# WL-DAC.net
KiCad netlist of a schematic drawn in Altium Designer
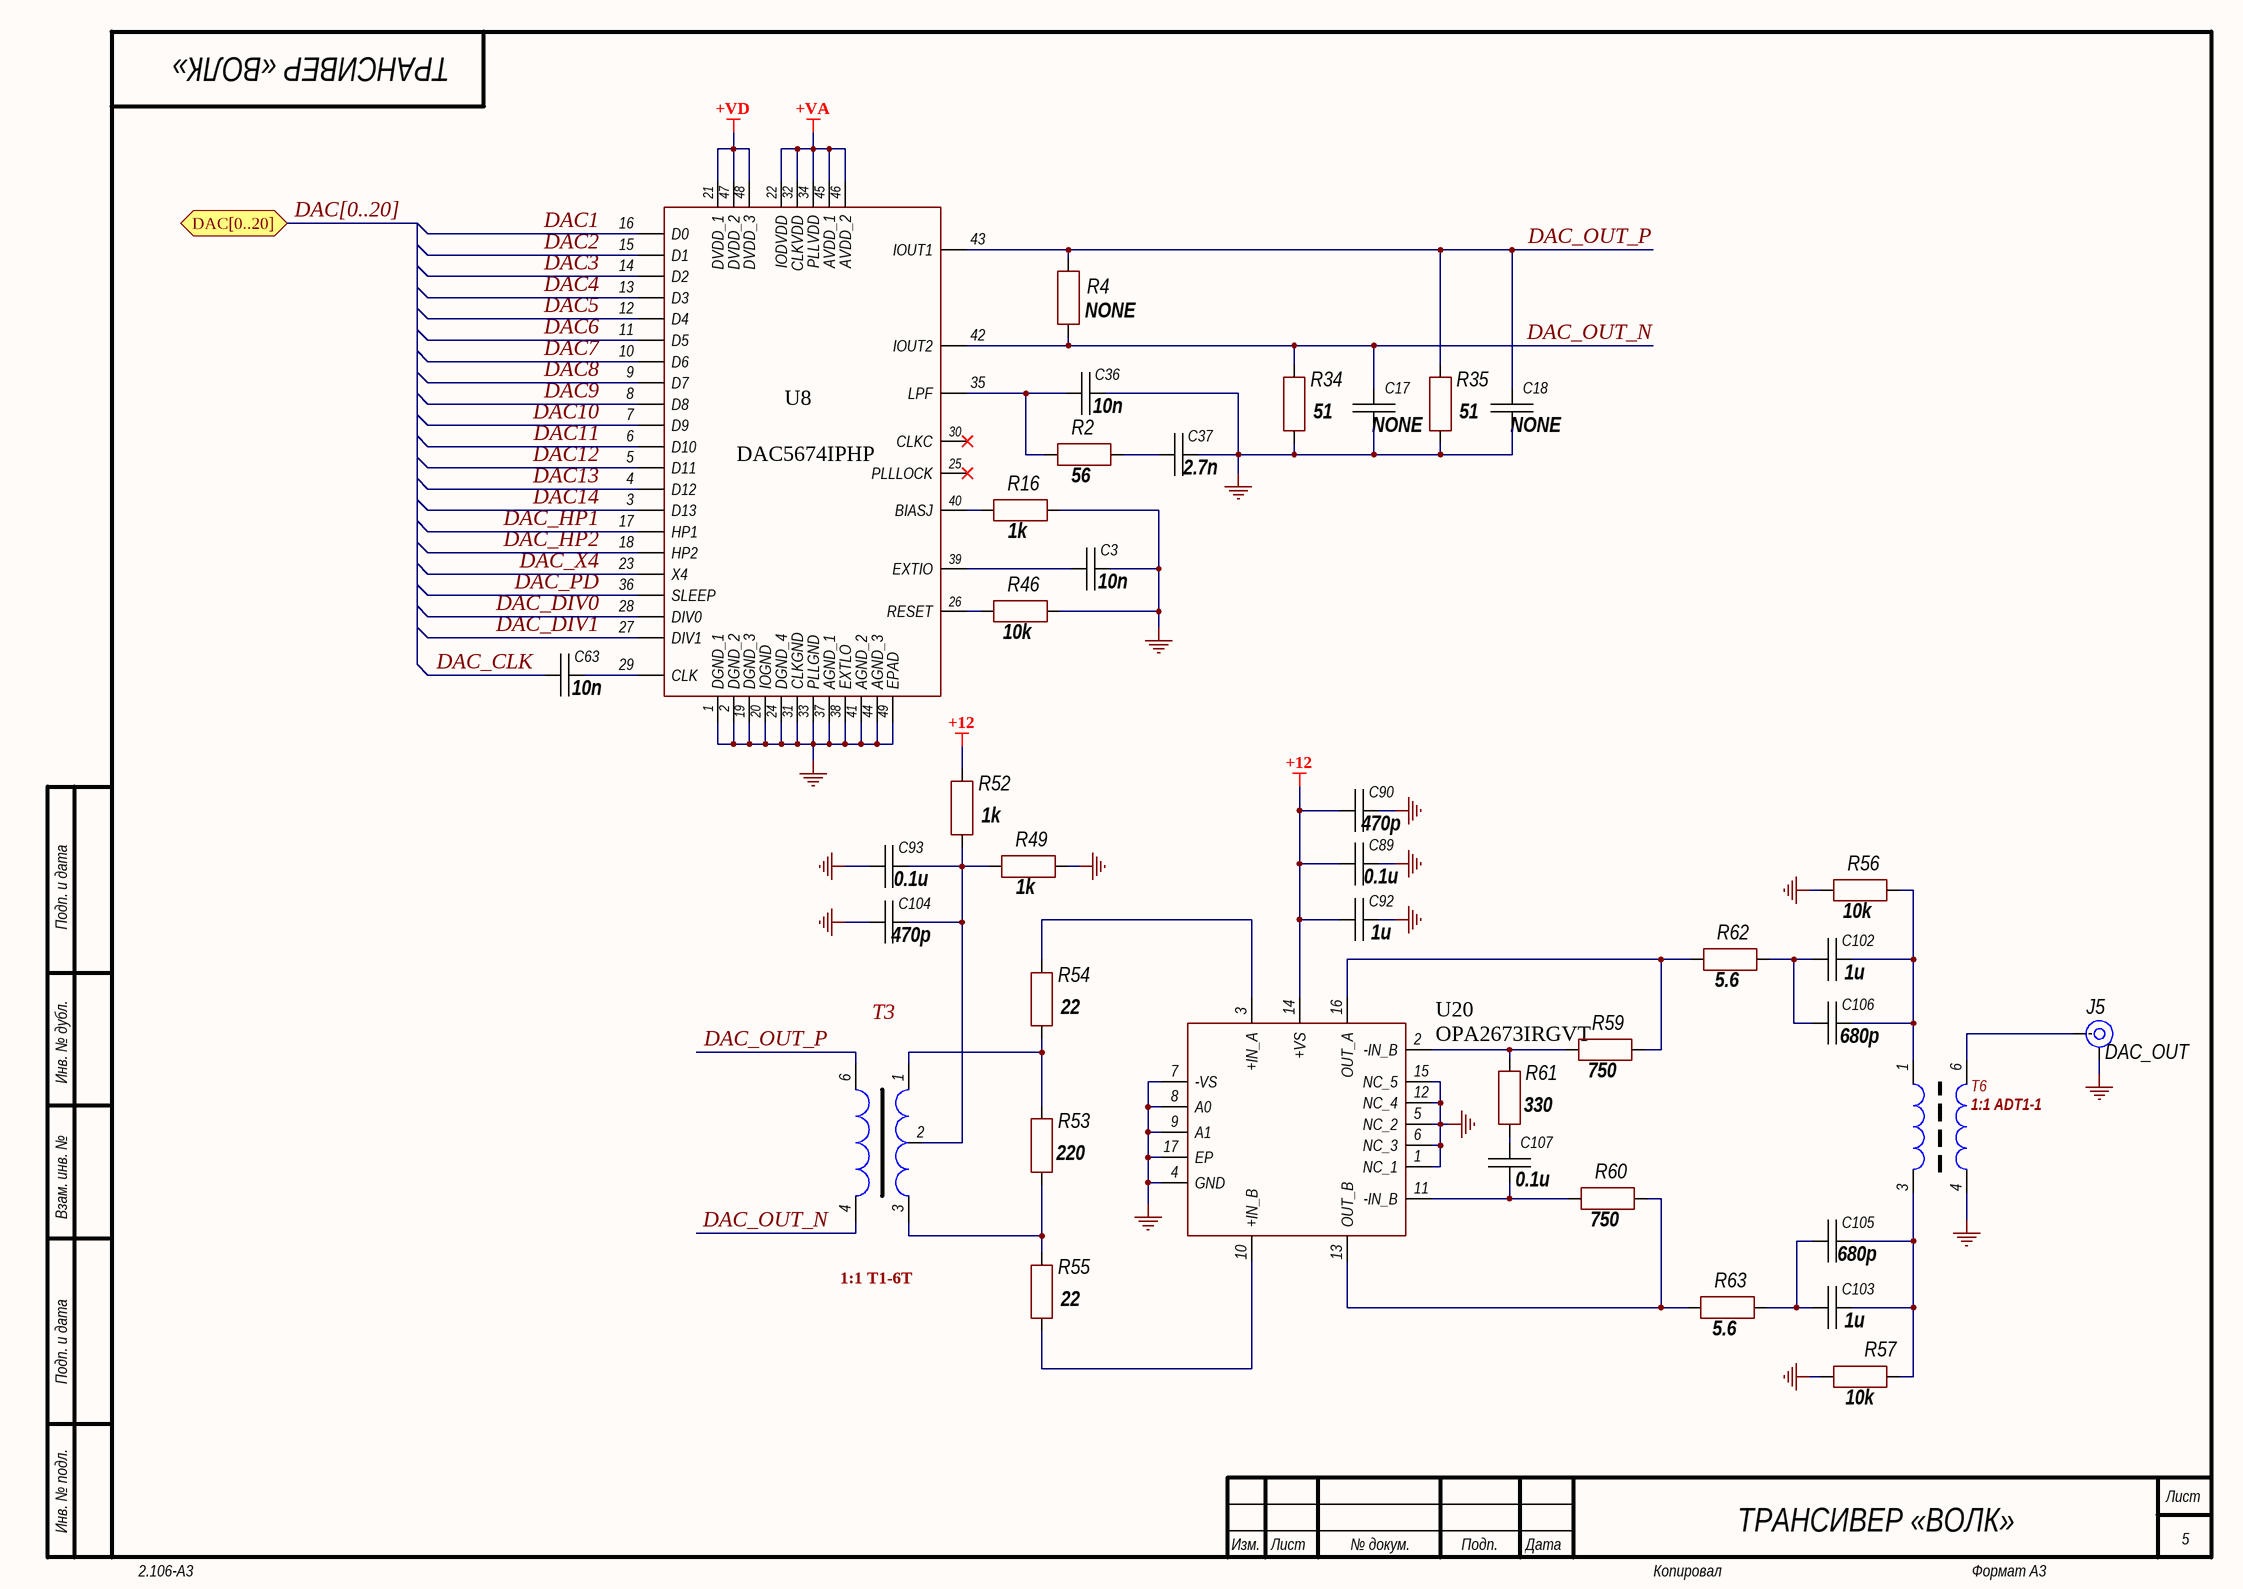
[diagram p0: WL-DAC.SchDoc]

(export (version "E")
  (design (tool "Eeschema 10.0.6"))
  (components
    (comp (ref "C3")
      (value "10n")
      (footprint "standard:CH0805C")
      (libsource (lib "Discrete") (part "Capacitor"))
    )
    (comp (ref "C17")
      (value "NONE")
      (footprint "standard:CH0805C")
      (libsource (lib "Discrete") (part "Capacitor"))
    )
    (comp (ref "C18")
      (value "NONE")
      (footprint "standard:CH0805C")
      (libsource (lib "Discrete") (part "Capacitor"))
    )
    (comp (ref "C36")
      (value "10n")
      (footprint "standard:CH0805C")
      (libsource (lib "Discrete") (part "Capacitor"))
    )
    (comp (ref "C37")
      (value "2.7n")
      (footprint "standard:CH0805C")
      (libsource (lib "Discrete") (part "Capacitor"))
    )
    (comp (ref "C63")
      (value "10n")
      (footprint "standard:CH0805C")
      (libsource (lib "Discrete") (part "Capacitor"))
    )
    (comp (ref "C89") (value "0.1u") (footprint "standard:CH0805C") (libsource (lib "") (part "Capacitor_1")))
    (comp (ref "C90") (value "470p") (footprint "standard:CH0805C") (libsource (lib "") (part "Capacitor_1")))
    (comp (ref "C92") (value "1u") (footprint "standard:CH0805C") (libsource (lib "") (part "Capacitor_1")))
    (comp (ref "C93")
      (value "0.1u")
      (footprint "standard:CH0805C")
      (libsource (lib "Discrete") (part "Capacitor"))
    )
    (comp (ref "C102")
      (value "1u")
      (footprint "standard:CH0805C")
      (libsource (lib "Discrete") (part "Capacitor"))
    )
    (comp (ref "C103")
      (value "1u")
      (footprint "standard:CH0805C")
      (libsource (lib "Discrete") (part "Capacitor"))
    )
    (comp (ref "C104")
      (value "470p")
      (footprint "standard:CH0805C")
      (libsource (lib "Discrete") (part "Capacitor"))
    )
    (comp (ref "C105")
      (value "680p")
      (footprint "standard:CH0805C")
      (libsource (lib "Discrete") (part "Capacitor"))
    )
    (comp (ref "C106")
      (value "680p")
      (footprint "standard:CH0805C")
      (libsource (lib "Discrete") (part "Capacitor"))
    )
    (comp (ref "C107")
      (value "0.1u")
      (footprint "standard:CH0805C")
      (libsource (lib "Discrete") (part "Capacitor"))
    )
    (comp (ref "J5")
      (value "DAC_OUT")
      (footprint "custom:CON: SMA")
      (description "RF")
      (libsource (lib "Connectors") (part "SMA"))
    )
    (comp (ref "R2") (value "56") (footprint "standard:CH0805R") (libsource (lib "") (part "Resistor_1")))
    (comp (ref "R4")
      (value "NONE")
      (footprint "standard:CH0805R")
      (libsource (lib "Discrete") (part "Resistor"))
    )
    (comp (ref "R16") (value "1k") (footprint "standard:CH0805R") (libsource (lib "") (part "Resistor_1")))
    (comp (ref "R34")
      (value "51")
      (footprint "standard:CH0805R")
      (libsource (lib "Discrete") (part "Resistor"))
    )
    (comp (ref "R35")
      (value "51")
      (footprint "standard:CH0805R")
      (libsource (lib "Discrete") (part "Resistor"))
    )
    (comp (ref "R46") (value "10k") (footprint "standard:CH0805R") (libsource (lib "") (part "Resistor_1")))
    (comp (ref "R49") (value "1k") (footprint "standard:CH0805R") (libsource (lib "") (part "Resistor_1")))
    (comp (ref "R52")
      (value "1k")
      (footprint "standard:CH0805R")
      (libsource (lib "Discrete") (part "Resistor"))
    )
    (comp (ref "R53")
      (value "220")
      (footprint "standard:CH0805R")
      (libsource (lib "Discrete") (part "Resistor"))
    )
    (comp (ref "R54")
      (value "22")
      (footprint "standard:CH0805R")
      (libsource (lib "Discrete") (part "Resistor"))
    )
    (comp (ref "R55")
      (value "22")
      (footprint "standard:CH0805R")
      (libsource (lib "Discrete") (part "Resistor"))
    )
    (comp (ref "R56") (value "10k") (footprint "standard:CH0805R") (libsource (lib "") (part "Resistor_1")))
    (comp (ref "R57")
      (value "10k")
      (footprint "standard:CH0805R")
      (libsource (lib "Discrete") (part "Resistor"))
    )
    (comp (ref "R59") (value "750") (footprint "standard:CH0805R") (libsource (lib "") (part "Resistor_1")))
    (comp (ref "R60") (value "750") (footprint "standard:CH0805R") (libsource (lib "") (part "Resistor_1")))
    (comp (ref "R61")
      (value "330")
      (footprint "standard:CH0805R")
      (libsource (lib "Discrete") (part "Resistor"))
    )
    (comp (ref "R62") (value "5.6") (footprint "standard:CH0805R") (libsource (lib "") (part "Resistor_1")))
    (comp (ref "R63") (value "5.6") (footprint "standard:CH0805R") (libsource (lib "") (part "Resistor_1")))
    (comp (ref "T3") (value "1:1 T1-6T") (footprint "TC1-4") (libsource (lib "Transformers") (part "TC4-1")))
    (comp (ref "T6")
      (value "1:1 ADT1-1")
      (footprint "TC1-4")
      (libsource (lib "Transformers") (part "BN-43-302"))
    )
    (comp (ref "U8")
      (value "DAC5674IPHP")
      (footprint "48-TQFP")
      (libsource (lib "Digital") (part "DAC5674IPHP"))
    )
    (comp (ref "U20")
      (value "OPA2673IRGVT")
      (footprint "16-QFN 4x4 PAD17")
      (libsource (lib "Digital") (part "OPA2673IRGVT"))
    )
  )
  (nets
    (net (code "8") (name "+12") (class "Default")
      (node (ref "C89") (pin "2") (pinfunction "2_2") (pintype "power_in"))
      (node (ref "C90") (pin "2") (pinfunction "2_2") (pintype "power_in"))
      (node (ref "C92") (pin "2") (pinfunction "2_2") (pintype "power_in"))
      (node (ref "R52") (pin "1") (pinfunction "1_1") (pintype "passive"))
      (node (ref "U20") (pin "14") (pinfunction "+VS_14") (pintype "passive"))
    )
    (net (code "9") (name "+VA") (class "Default")
      (node (ref "U8") (pin "22") (pinfunction "IODVDD_22") (pintype "power_in"))
      (node (ref "U8") (pin "32") (pinfunction "CLKVDD_32") (pintype "power_in"))
      (node (ref "U8") (pin "34") (pinfunction "PLLVDD_34") (pintype "power_in"))
      (node (ref "U8") (pin "45") (pinfunction "AVDD_1_45") (pintype "power_in"))
      (node (ref "U8") (pin "46") (pinfunction "AVDD_2_46") (pintype "power_in"))
    )
    (net (code "10") (name "+VD") (class "Default")
      (node (ref "U8") (pin "21") (pinfunction "DVDD_1_21") (pintype "power_in"))
      (node (ref "U8") (pin "47") (pinfunction "DVDD_2_47") (pintype "power_in"))
      (node (ref "U8") (pin "48") (pinfunction "DVDD_3_48") (pintype "power_in"))
    )
    (net (code "11") (name "/DAC1") (class "Default")
      (node (ref "U8") (pin "16") (pinfunction "D0_16") (pintype "power_in"))
    )
    (net (code "12") (name "/DAC2") (class "Default")
      (node (ref "U8") (pin "15") (pinfunction "D1_15") (pintype "power_in"))
    )
    (net (code "13") (name "/DAC3") (class "Default")
      (node (ref "U8") (pin "14") (pinfunction "D2_14") (pintype "power_in"))
    )
    (net (code "14") (name "/DAC4") (class "Default")
      (node (ref "U8") (pin "13") (pinfunction "D3_13") (pintype "power_in"))
    )
    (net (code "15") (name "/DAC5") (class "Default")
      (node (ref "U8") (pin "12") (pinfunction "D4_12") (pintype "power_in"))
    )
    (net (code "16") (name "/DAC6") (class "Default")
      (node (ref "U8") (pin "11") (pinfunction "D5_11") (pintype "power_in"))
    )
    (net (code "17") (name "/DAC7") (class "Default")
      (node (ref "U8") (pin "10") (pinfunction "D6_10") (pintype "power_in"))
    )
    (net (code "18") (name "/DAC8") (class "Default")
      (node (ref "U8") (pin "9") (pinfunction "D7_9") (pintype "power_in"))
    )
    (net (code "19") (name "/DAC9") (class "Default")
      (node (ref "U8") (pin "8") (pinfunction "D8_8") (pintype "power_in"))
    )
    (net (code "20") (name "/DAC10") (class "Default")
      (node (ref "U8") (pin "7") (pinfunction "D9_7") (pintype "power_in"))
    )
    (net (code "21") (name "/DAC11") (class "Default")
      (node (ref "U8") (pin "6") (pinfunction "D10_6") (pintype "power_in"))
    )
    (net (code "22") (name "/DAC12") (class "Default")
      (node (ref "U8") (pin "5") (pinfunction "D11_5") (pintype "power_in"))
    )
    (net (code "23") (name "/DAC13") (class "Default")
      (node (ref "U8") (pin "4") (pinfunction "D12_4") (pintype "power_in"))
    )
    (net (code "24") (name "/DAC14") (class "Default")
      (node (ref "U8") (pin "3") (pinfunction "D13_3") (pintype "power_in"))
    )
    (net (code "26") (name "/DAC_CLK") (class "Default")
      (node (ref "C63") (pin "2") (pinfunction "2_2") (pintype "power_in"))
    )
    (net (code "27") (name "/DAC_DIV0") (class "Default")
      (node (ref "U8") (pin "28") (pinfunction "DIV0_28") (pintype "power_in"))
    )
    (net (code "28") (name "/DAC_DIV1") (class "Default")
      (node (ref "U8") (pin "27") (pinfunction "DIV1_27") (pintype "power_in"))
    )
    (net (code "29") (name "/DAC_HP1") (class "Default")
      (node (ref "U8") (pin "17") (pinfunction "HP1_17") (pintype "power_in"))
    )
    (net (code "30") (name "/DAC_HP2") (class "Default")
      (node (ref "U8") (pin "18") (pinfunction "HP2_18") (pintype "power_in"))
    )
    (net (code "31") (name "/DAC_OUT_N") (class "Default")
      (node (ref "C17") (pin "1") (pinfunction "1_1") (pintype "power_in"))
      (node (ref "R34") (pin "1") (pinfunction "1_1") (pintype "passive"))
      (node (ref "R4") (pin "2") (pinfunction "2_2") (pintype "passive"))
      (node (ref "T3") (pin "4") (pinfunction "4_4") (pintype "power_in"))
      (node (ref "U8") (pin "42") (pinfunction "IOUT2_42") (pintype "passive"))
    )
    (net (code "32") (name "/DAC_OUT_P") (class "Default")
      (node (ref "C18") (pin "1") (pinfunction "1_1") (pintype "power_in"))
      (node (ref "R35") (pin "1") (pinfunction "1_1") (pintype "passive"))
      (node (ref "R4") (pin "1") (pinfunction "1_1") (pintype "passive"))
      (node (ref "T3") (pin "6") (pinfunction "6_6") (pintype "power_in"))
      (node (ref "U8") (pin "43") (pinfunction "IOUT1_43") (pintype "passive"))
    )
    (net (code "33") (name "/DAC_PD") (class "Default")
      (node (ref "U8") (pin "36") (pinfunction "SLEEP_36") (pintype "power_in"))
    )
    (net (code "34") (name "/DAC_X4") (class "Default")
      (node (ref "U8") (pin "23") (pinfunction "X4_23") (pintype "power_in"))
    )
    (net (code "35") (name "GND") (class "Default")
      (node (ref "C104") (pin "2") (pinfunction "2_2") (pintype "power_in"))
      (node (ref "C17") (pin "2") (pinfunction "2_2") (pintype "power_in"))
      (node (ref "C18") (pin "2") (pinfunction "2_2") (pintype "power_in"))
      (node (ref "C3") (pin "1") (pinfunction "1_1") (pintype "power_in"))
      (node (ref "C36") (pin "1") (pinfunction "1_1") (pintype "power_in"))
      (node (ref "C37") (pin "1") (pinfunction "1_1") (pintype "power_in"))
      (node (ref "C89") (pin "1") (pinfunction "1_1") (pintype "power_in"))
      (node (ref "C90") (pin "1") (pinfunction "1_1") (pintype "power_in"))
      (node (ref "C92") (pin "1") (pinfunction "1_1") (pintype "power_in"))
      (node (ref "C93") (pin "2") (pinfunction "2_2") (pintype "power_in"))
      (node (ref "J5") (pin "2") (pinfunction "IN_2") (pintype "passive"))
      (node (ref "R16") (pin "1") (pinfunction "1_1") (pintype "passive"))
      (node (ref "R34") (pin "2") (pinfunction "2_2") (pintype "passive"))
      (node (ref "R35") (pin "2") (pinfunction "2_2") (pintype "passive"))
      (node (ref "R46") (pin "1") (pinfunction "1_1") (pintype "passive"))
      (node (ref "R49") (pin "1") (pinfunction "1_1") (pintype "passive"))
      (node (ref "R56") (pin "2") (pinfunction "2_2") (pintype "passive"))
      (node (ref "R57") (pin "2") (pinfunction "2_2") (pintype "passive"))
      (node (ref "T6") (pin "4") (pinfunction "4_4") (pintype "passive"))
      (node (ref "U20") (pin "1") (pinfunction "NC_1_1") (pintype "passive"))
      (node (ref "U20") (pin "12") (pinfunction "NC_4_12") (pintype "passive"))
      (node (ref "U20") (pin "15") (pinfunction "NC_5_15") (pintype "passive"))
      (node (ref "U20") (pin "17") (pinfunction "EP_17") (pintype "passive"))
      (node (ref "U20") (pin "4") (pinfunction "GND_4") (pintype "passive"))
      (node (ref "U20") (pin "5") (pinfunction "NC_2_5") (pintype "passive"))
      (node (ref "U20") (pin "6") (pinfunction "NC_3_6") (pintype "passive"))
      (node (ref "U20") (pin "7") (pinfunction "-VS_7") (pintype "passive"))
      (node (ref "U20") (pin "8") (pinfunction "A0_8") (pintype "passive"))
      (node (ref "U20") (pin "9") (pinfunction "A1_9") (pintype "passive"))
      (node (ref "U8") (pin "1") (pinfunction "DGND_1_1") (pintype "power_in"))
      (node (ref "U8") (pin "19") (pinfunction "DGND_3_19") (pintype "power_in"))
      (node (ref "U8") (pin "2") (pinfunction "DGND_2_2") (pintype "power_in"))
      (node (ref "U8") (pin "20") (pinfunction "IOGND_20") (pintype "power_in"))
      (node (ref "U8") (pin "24") (pinfunction "DGND_4_24") (pintype "power_in"))
      (node (ref "U8") (pin "31") (pinfunction "CLKGND_31") (pintype "power_in"))
      (node (ref "U8") (pin "33") (pinfunction "PLLGND_33") (pintype "power_in"))
      (node (ref "U8") (pin "37") (pinfunction "AGND_1_37") (pintype "power_in"))
      (node (ref "U8") (pin "38") (pinfunction "EXTLO_38") (pintype "power_in"))
      (node (ref "U8") (pin "41") (pinfunction "AGND_2_41") (pintype "power_in"))
      (node (ref "U8") (pin "44") (pinfunction "AGND_3_44") (pintype "power_in"))
      (node (ref "U8") (pin "49") (pinfunction "EPAD_49") (pintype "power_in"))
    )
    (net (code "36") (name "Net-(C37-Pad2)") (class "Default")
      (node (ref "C37") (pin "2") (pinfunction "2_2") (pintype "power_in"))
      (node (ref "R2") (pin "1") (pinfunction "1_1") (pintype "passive"))
    )
    (net (code "37") (name "Net-(C102-Pad1)") (class "Default")
      (node (ref "C102") (pin "1") (pinfunction "1_1") (pintype "power_in"))
      (node (ref "C106") (pin "1") (pinfunction "1_1") (pintype "power_in"))
      (node (ref "R56") (pin "1") (pinfunction "1_1") (pintype "passive"))
      (node (ref "T6") (pin "1") (pinfunction "1_1") (pintype "passive"))
    )
    (net (code "38") (name "Net-(C102-Pad2)") (class "Default")
      (node (ref "C102") (pin "2") (pinfunction "2_2") (pintype "power_in"))
      (node (ref "C106") (pin "2") (pinfunction "2_2") (pintype "power_in"))
      (node (ref "R62") (pin "1") (pinfunction "1_1") (pintype "passive"))
    )
    (net (code "39") (name "Net-(C103-Pad1)") (class "Default")
      (node (ref "C103") (pin "1") (pinfunction "1_1") (pintype "power_in"))
      (node (ref "C105") (pin "1") (pinfunction "1_1") (pintype "power_in"))
      (node (ref "R57") (pin "1") (pinfunction "1_1") (pintype "passive"))
      (node (ref "T6") (pin "3") (pinfunction "3_3") (pintype "passive"))
    )
    (net (code "40") (name "Net-(C103-Pad2)") (class "Default")
      (node (ref "C103") (pin "2") (pinfunction "2_2") (pintype "power_in"))
      (node (ref "C105") (pin "2") (pinfunction "2_2") (pintype "power_in"))
      (node (ref "R63") (pin "1") (pinfunction "1_1") (pintype "passive"))
    )
    (net (code "41") (name "Net-(C104-Pad1)") (class "Default")
      (node (ref "C104") (pin "1") (pinfunction "1_1") (pintype "power_in"))
      (node (ref "C93") (pin "1") (pinfunction "1_1") (pintype "power_in"))
      (node (ref "R49") (pin "2") (pinfunction "2_2") (pintype "passive"))
      (node (ref "R52") (pin "2") (pinfunction "2_2") (pintype "passive"))
      (node (ref "T3") (pin "2") (pinfunction "2_2") (pintype "power_in"))
    )
    (net (code "42") (name "Net-(C107-Pad1)") (class "Default")
      (node (ref "C107") (pin "1") (pinfunction "1_1") (pintype "power_in"))
      (node (ref "R61") (pin "2") (pinfunction "2_2") (pintype "passive"))
    )
    (net (code "43") (name "Net-(C107-Pad2)") (class "Default")
      (node (ref "C107") (pin "2") (pinfunction "2_2") (pintype "power_in"))
      (node (ref "R60") (pin "2") (pinfunction "2_2") (pintype "passive"))
      (node (ref "U20") (pin "11") (pinfunction "-IN_B_11") (pintype "passive"))
    )
    (net (code "44") (name "Net-(J5-IN-Pad1)") (class "Default")
      (node (ref "J5") (pin "1") (pinfunction "IN_1") (pintype "passive"))
      (node (ref "T6") (pin "6") (pinfunction "6_6") (pintype "passive"))
    )
    (net (code "45") (name "Net-(R53-Pad1)") (class "Default")
      (node (ref "R53") (pin "1") (pinfunction "1_1") (pintype "passive"))
      (node (ref "R54") (pin "2") (pinfunction "2_2") (pintype "passive"))
      (node (ref "T3") (pin "1") (pinfunction "1_1") (pintype "power_in"))
    )
    (net (code "46") (name "Net-(R53-Pad2)") (class "Default")
      (node (ref "R53") (pin "2") (pinfunction "2_2") (pintype "passive"))
      (node (ref "R55") (pin "1") (pinfunction "1_1") (pintype "passive"))
      (node (ref "T3") (pin "3") (pinfunction "3_3") (pintype "power_in"))
    )
    (net (code "47") (name "Net-(R59-Pad2)") (class "Default")
      (node (ref "R59") (pin "2") (pinfunction "2_2") (pintype "passive"))
      (node (ref "R61") (pin "1") (pinfunction "1_1") (pintype "passive"))
      (node (ref "U20") (pin "2") (pinfunction "-IN_B_2") (pintype "passive"))
    )
    (net (code "48") (name "Net-(U8-BIASJ)") (class "Default")
      (node (ref "R16") (pin "2") (pinfunction "2_2") (pintype "passive"))
      (node (ref "U8") (pin "40") (pinfunction "BIASJ_40") (pintype "power_in"))
    )
    (net (code "49") (name "Net-(U8-CLK)") (class "Default")
      (node (ref "C63") (pin "1") (pinfunction "1_1") (pintype "power_in"))
      (node (ref "U8") (pin "29") (pinfunction "CLK_29") (pintype "power_in"))
    )
    (net (code "50") (name "Net-(U8-EXTIO)") (class "Default")
      (node (ref "C3") (pin "2") (pinfunction "2_2") (pintype "power_in"))
      (node (ref "U8") (pin "39") (pinfunction "EXTIO_39") (pintype "power_in"))
    )
    (net (code "51") (name "Net-(U8-LPF)") (class "Default")
      (node (ref "C36") (pin "2") (pinfunction "2_2") (pintype "power_in"))
      (node (ref "R2") (pin "2") (pinfunction "2_2") (pintype "passive"))
      (node (ref "U8") (pin "35") (pinfunction "LPF_35") (pintype "passive"))
    )
    (net (code "52") (name "Net-(U8-RESET)") (class "Default")
      (node (ref "R46") (pin "2") (pinfunction "2_2") (pintype "passive"))
      (node (ref "U8") (pin "26") (pinfunction "RESET_26") (pintype "power_in"))
    )
    (net (code "53") (name "Net-(U20-+IN_A)") (class "Default")
      (node (ref "R54") (pin "1") (pinfunction "1_1") (pintype "passive"))
      (node (ref "U20") (pin "3") (pinfunction "+IN_A_3") (pintype "passive"))
    )
    (net (code "54") (name "Net-(U20-+IN_B)") (class "Default")
      (node (ref "R55") (pin "2") (pinfunction "2_2") (pintype "passive"))
      (node (ref "U20") (pin "10") (pinfunction "+IN_B_10") (pintype "passive"))
    )
    (net (code "55") (name "Net-(U20-OUT_A)") (class "Default")
      (node (ref "R59") (pin "1") (pinfunction "1_1") (pintype "passive"))
      (node (ref "R62") (pin "2") (pinfunction "2_2") (pintype "passive"))
      (node (ref "U20") (pin "16") (pinfunction "OUT_A_16") (pintype "passive"))
    )
    (net (code "56") (name "Net-(U20-OUT_B)") (class "Default")
      (node (ref "R60") (pin "1") (pinfunction "1_1") (pintype "passive"))
      (node (ref "R63") (pin "2") (pinfunction "2_2") (pintype "passive"))
      (node (ref "U20") (pin "13") (pinfunction "OUT_B_13") (pintype "passive"))
    )
    (net (code "57") (name "unconnected-(U8-CLKC-Pad30)") (class "Default")
      (node (ref "U8") (pin "30") (pinfunction "CLKC_30") (pintype "power_in+no_connect"))
    )
    (net (code "58") (name "unconnected-(U8-PLLLOCK-Pad25)") (class "Default")
      (node (ref "U8") (pin "25") (pinfunction "PLLLOCK_25") (pintype "power_in+no_connect"))
    )
  )
)
